# Adafruit_BMP180.net
KiCad netlist of a schematic drawn in EAGLE
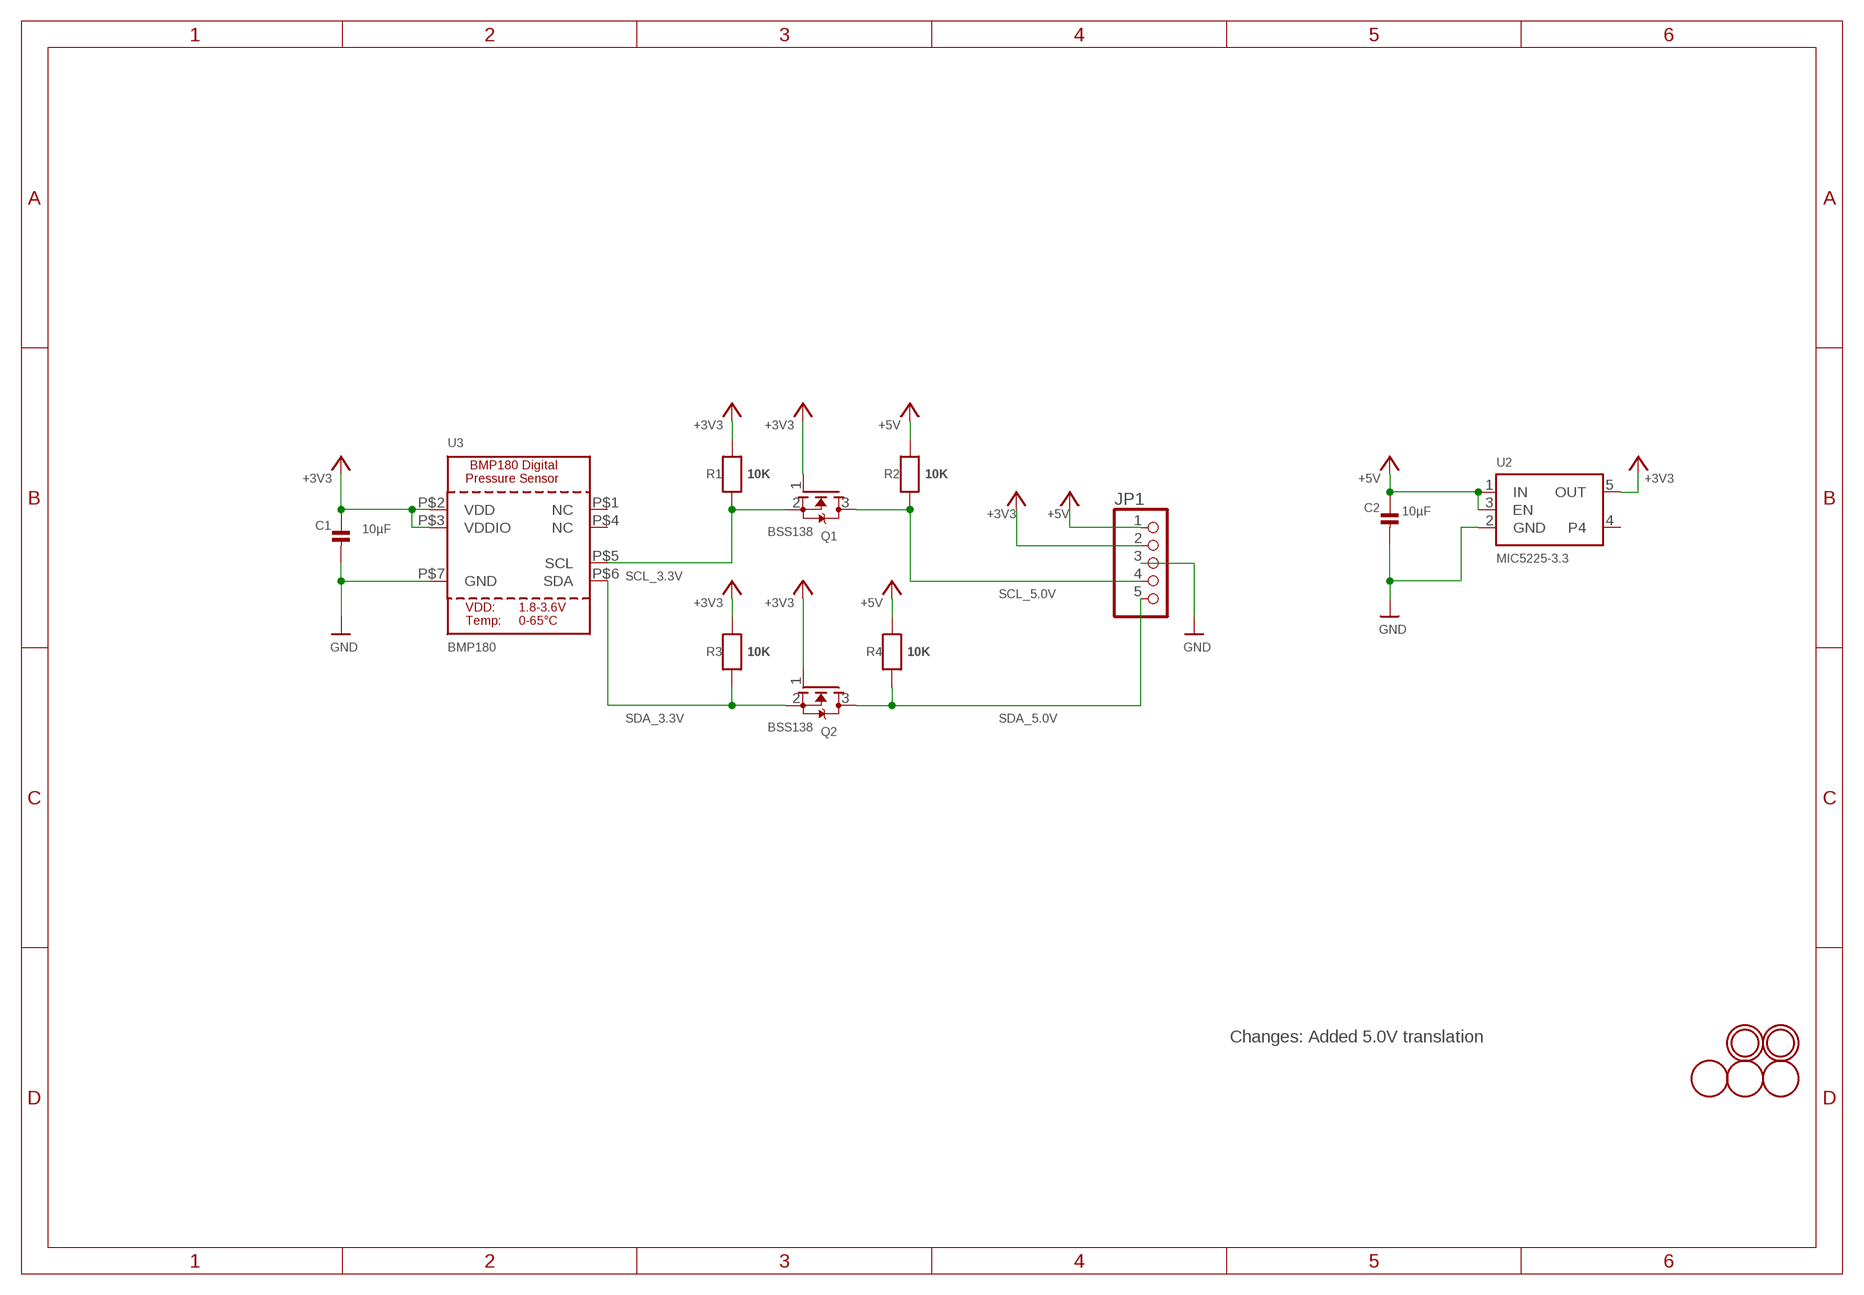
[diagram p0: schematic, sheet 1]

(export (version "E")
  (design (tool "Eeschema 10.0.6"))
  (components
    (comp (ref "C1")
      (value "10µF")
      (footprint "eagle-import:0805-NO")
      (libsource (lib "eagle-import") (part "CAP_CERAMIC0805-NOOUTLINE"))
    )
    (comp (ref "C2")
      (value "10µF")
      (footprint "eagle-import:0805-NO")
      (libsource (lib "eagle-import") (part "CAP_CERAMIC0805-NOOUTLINE"))
    )
    (comp (ref "JP1")
      (value "HEADER-1X570MIL")
      (footprint "eagle-import:1X05_ROUND_70")
      (libsource (lib "eagle-import") (part "HEADER-1X570MIL"))
    )
    (comp (ref "Q1")
      (value "BSS138")
      (footprint "eagle-import:SOT23")
      (libsource (lib "eagle-import") (part "MOSFET-NREFLOW"))
    )
    (comp (ref "Q2")
      (value "BSS138")
      (footprint "eagle-import:SOT23")
      (libsource (lib "eagle-import") (part "MOSFET-NREFLOW"))
    )
    (comp (ref "R1")
      (value "10K")
      (footprint "eagle-import:0805-NO")
      (libsource (lib "eagle-import") (part "RESISTOR0805_NOOUTLINE"))
    )
    (comp (ref "R2")
      (value "10K")
      (footprint "eagle-import:_0805MP")
      (libsource (lib "eagle-import") (part "RESISTOR_0805MP"))
    )
    (comp (ref "R3")
      (value "10K")
      (footprint "eagle-import:0805-NO")
      (libsource (lib "eagle-import") (part "RESISTOR0805_NOOUTLINE"))
    )
    (comp (ref "R4")
      (value "10K")
      (footprint "eagle-import:0805-NO")
      (libsource (lib "eagle-import") (part "RESISTOR0805_NOOUTLINE"))
    )
    (comp (ref "U$1")
      (value "FIDUCIAL")
      (footprint "eagle-import:FIDUCIAL_1MM")
      (libsource (lib "eagle-import") (part "FIDUCIAL"))
    )
    (comp (ref "U$5")
      (value "FIDUCIAL")
      (footprint "eagle-import:FIDUCIAL_1MM")
      (libsource (lib "eagle-import") (part "FIDUCIAL"))
    )
    (comp (ref "U$7")
      (value "MOUNTINGHOLE2.0")
      (footprint "eagle-import:MOUNTINGHOLE_2.0_PLATED")
      (libsource (lib "eagle-import") (part "MOUNTINGHOLE2.0"))
    )
    (comp (ref "U$8")
      (value "MOUNTINGHOLE2.0")
      (footprint "eagle-import:MOUNTINGHOLE_2.0_PLATED")
      (libsource (lib "eagle-import") (part "MOUNTINGHOLE2.0"))
    )
    (comp (ref "U$15")
      (value "FIDUCIAL")
      (footprint "eagle-import:FIDUCIAL_1MM")
      (libsource (lib "eagle-import") (part "FIDUCIAL"))
    )
    (comp (ref "U2")
      (value "MIC5225-3.3")
      (footprint "eagle-import:SOT23-5")
      (libsource (lib "eagle-import") (part "VREG_SOT23-5"))
    )
    (comp (ref "U3")
      (value "BMP180")
      (footprint "eagle-import:BMP180_EXTENDED")
      (libsource (lib "eagle-import") (part "BMP180EXT"))
    )
  )
  (nets
    (net (code "1") (name "+3V3") (class "Default")
      (node (ref "C1") (pin "1") (pinfunction "1_1") (pintype "passive"))
      (node (ref "JP1") (pin "2") (pinfunction "2_2") (pintype "passive"))
      (node (ref "Q1") (pin "1") (pinfunction "G_1") (pintype "bidirectional"))
      (node (ref "Q2") (pin "1") (pinfunction "G_1") (pintype "bidirectional"))
      (node (ref "R1") (pin "2") (pinfunction "2_2") (pintype "passive"))
      (node (ref "R3") (pin "2") (pinfunction "2_2") (pintype "passive"))
      (node (ref "U2") (pin "5") (pinfunction "OUT_5") (pintype "power_in"))
      (node (ref "U3") (pin "P$2") (pinfunction "VDD_P$2") (pintype "power_in"))
      (node (ref "U3") (pin "P$3") (pinfunction "VDDIO_P$3") (pintype "power_in"))
    )
    (net (code "2") (name "+5V") (class "Default")
      (node (ref "C2") (pin "1") (pinfunction "1_1") (pintype "passive"))
      (node (ref "JP1") (pin "1") (pinfunction "1_1") (pintype "passive"))
      (node (ref "R2") (pin "2") (pinfunction "2_2") (pintype "passive"))
      (node (ref "R4") (pin "2") (pinfunction "2_2") (pintype "passive"))
      (node (ref "U2") (pin "1") (pinfunction "IN_1") (pintype "power_in"))
      (node (ref "U2") (pin "3") (pinfunction "EN_3") (pintype "input"))
    )
    (net (code "3") (name "/SCL_3.3V") (class "Default")
      (node (ref "Q1") (pin "2") (pinfunction "S_2") (pintype "bidirectional"))
      (node (ref "R1") (pin "1") (pinfunction "1_1") (pintype "passive"))
      (node (ref "U3") (pin "P$5") (pinfunction "SCL_P$5") (pintype "bidirectional"))
    )
    (net (code "4") (name "/SCL_5.0V") (class "Default")
      (node (ref "JP1") (pin "4") (pinfunction "4_4") (pintype "passive"))
      (node (ref "Q1") (pin "3") (pinfunction "D_3") (pintype "bidirectional"))
      (node (ref "R2") (pin "1") (pinfunction "1_1") (pintype "passive"))
    )
    (net (code "5") (name "/SDA_3.3V") (class "Default")
      (node (ref "Q2") (pin "2") (pinfunction "S_2") (pintype "bidirectional"))
      (node (ref "R3") (pin "1") (pinfunction "1_1") (pintype "passive"))
      (node (ref "U3") (pin "P$6") (pinfunction "SDA_P$6") (pintype "bidirectional"))
    )
    (net (code "6") (name "/SDA_5.0V") (class "Default")
      (node (ref "JP1") (pin "5") (pinfunction "5_5") (pintype "passive"))
      (node (ref "Q2") (pin "3") (pinfunction "D_3") (pintype "bidirectional"))
      (node (ref "R4") (pin "1") (pinfunction "1_1") (pintype "passive"))
    )
    (net (code "7") (name "GND") (class "Default")
      (node (ref "C1") (pin "2") (pinfunction "2_2") (pintype "passive"))
      (node (ref "C2") (pin "2") (pinfunction "2_2") (pintype "passive"))
      (node (ref "JP1") (pin "3") (pinfunction "3_3") (pintype "passive"))
      (node (ref "U2") (pin "2") (pinfunction "GND_2") (pintype "power_in"))
      (node (ref "U3") (pin "P$7") (pinfunction "GND_P$7") (pintype "power_in"))
    )
    (net (code "8") (name "unconnected-(U2-P4-Pad4)") (class "Default")
      (node (ref "U2") (pin "4") (pinfunction "P4_4") (pintype "bidirectional"))
    )
    (net (code "9") (name "unconnected-(U3-NC-PadP$1)") (class "Default")
      (node (ref "U3") (pin "P$1") (pinfunction "NC_P$1") (pintype "no_connect"))
    )
    (net (code "10") (name "unconnected-(U3-NC-PadP$4)") (class "Default")
      (node (ref "U3") (pin "P$4") (pinfunction "NC_P$4") (pintype "no_connect"))
    )
  )
)
